# bbg.net
KiCad netlist of a schematic drawn in EAGLE
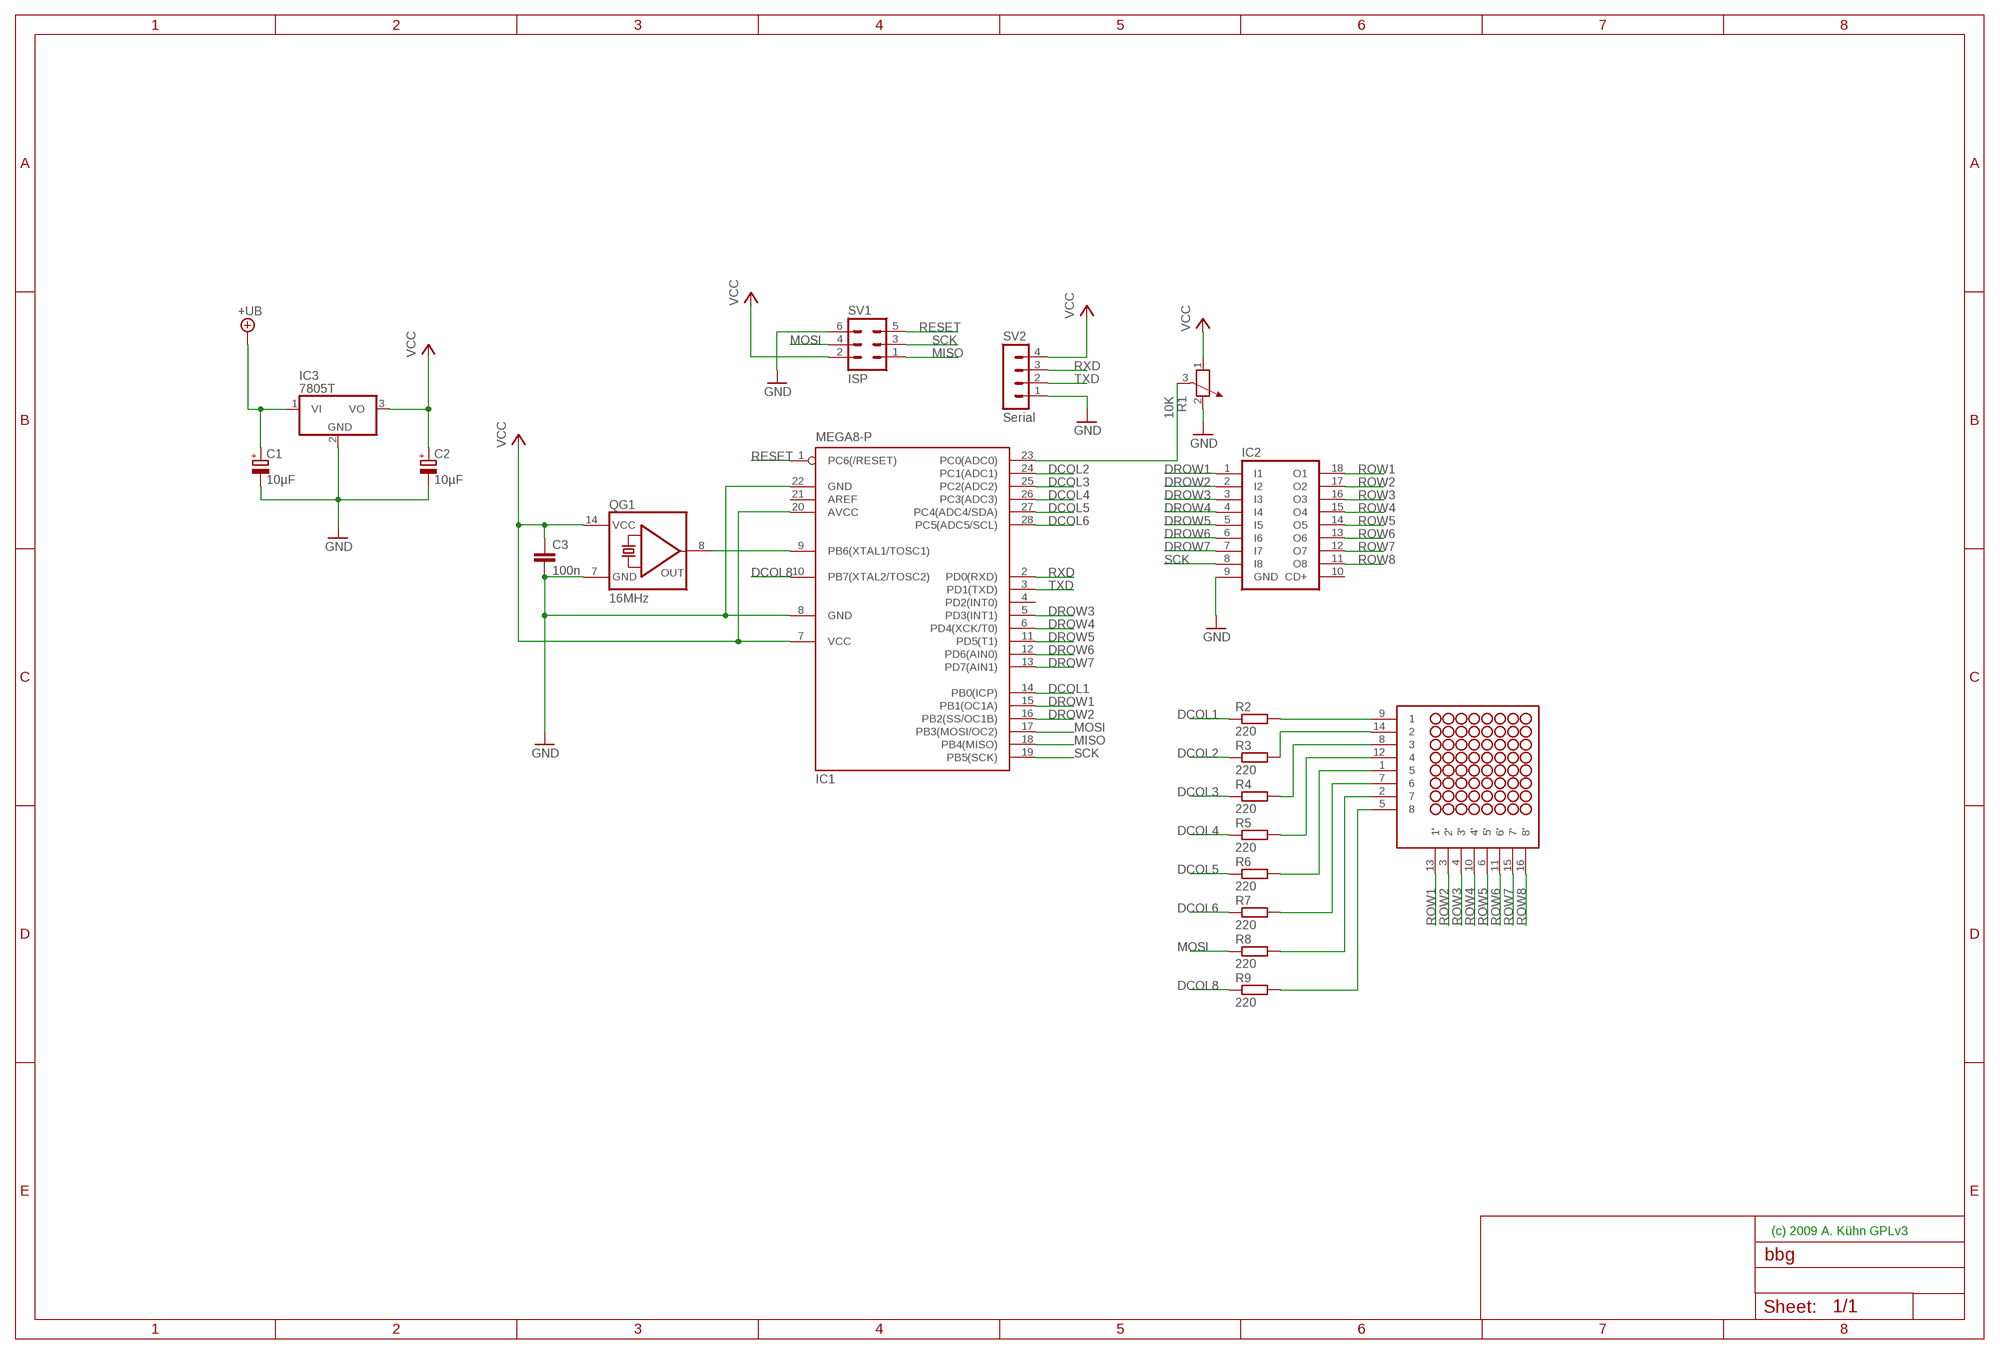
[diagram p0: schematic, sheet 1]

(export (version "E")
  (design (tool "Eeschema 10.0.6"))
  (components
    (comp (ref "C1")
      (value "10µF")
      (footprint "eagle-import:EB20D")
      (libsource (lib "eagle-import") (part "CPOL-EUE10-20"))
    )
    (comp (ref "C2")
      (value "10µF")
      (footprint "eagle-import:EB20D")
      (libsource (lib "eagle-import") (part "CPOL-EUE10-20"))
    )
    (comp (ref "C3")
      (value "100n")
      (footprint "eagle-import:C0603")
      (libsource (lib "eagle-import") (part "C-EUC0603"))
    )
    (comp (ref "IC1")
      (value "MEGA8-P")
      (footprint "eagle-import:DIL28-3")
      (libsource (lib "eagle-import") (part "MEGA8-P"))
    )
    (comp (ref "IC2")
      (value "ULN2803A")
      (footprint "eagle-import:DIL18")
      (libsource (lib "eagle-import") (part "ULN2803A"))
    )
    (comp (ref "IC3")
      (value "7805T")
      (footprint "eagle-import:TO220H")
      (libsource (lib "eagle-import") (part "78T05"))
    )
    (comp (ref "QG1")
      (value "16MHz")
      (footprint "eagle-import:DIL14S")
      (libsource (lib "eagle-import") (part "QG5860"))
    )
    (comp (ref "R1")
      (value "10K")
      (footprint "eagle-import:PT-10")
      (libsource (lib "eagle-import") (part "POTENTIOMETER_PT-10"))
    )
    (comp (ref "R2")
      (value "220")
      (footprint "eagle-import:0204V")
      (libsource (lib "eagle-import") (part "R-EU_0204/2V"))
    )
    (comp (ref "R3")
      (value "220")
      (footprint "eagle-import:0204V")
      (libsource (lib "eagle-import") (part "R-EU_0204/2V"))
    )
    (comp (ref "R4")
      (value "220")
      (footprint "eagle-import:0204V")
      (libsource (lib "eagle-import") (part "R-EU_0204/2V"))
    )
    (comp (ref "R5")
      (value "220")
      (footprint "eagle-import:0204V")
      (libsource (lib "eagle-import") (part "R-EU_0204/2V"))
    )
    (comp (ref "R6")
      (value "220")
      (footprint "eagle-import:0204V")
      (libsource (lib "eagle-import") (part "R-EU_0204/2V"))
    )
    (comp (ref "R7")
      (value "220")
      (footprint "eagle-import:0204V")
      (libsource (lib "eagle-import") (part "R-EU_0204/2V"))
    )
    (comp (ref "R8")
      (value "220")
      (footprint "eagle-import:0204V")
      (libsource (lib "eagle-import") (part "R-EU_0204/2V"))
    )
    (comp (ref "R9")
      (value "220")
      (footprint "eagle-import:0204V")
      (libsource (lib "eagle-import") (part "R-EU_0204/2V"))
    )
    (comp (ref "SV1")
      (value "ISP")
      (footprint "eagle-import:MA03-2")
      (libsource (lib "eagle-import") (part "MA03-2"))
    )
    (comp (ref "SV2")
      (value "Serial")
      (footprint "eagle-import:MA04-1")
      (libsource (lib "eagle-import") (part "MA04-1"))
    )
    (comp (ref "U$1")
      (value "NFM-12881BG-11")
      (footprint "eagle-import:NFM-12881BG-11")
      (libsource (lib "eagle-import") (part "NFM-12881BG-11"))
    )
  )
  (nets
    (net (code "1") (name "+UB") (class "Default")
      (node (ref "C1") (pin "+") (pinfunction "+_+") (pintype "passive"))
      (node (ref "IC3") (pin "1") (pinfunction "VI_1") (pintype "input"))
    )
    (net (code "2") (name "/DCOL1") (class "Default")
      (node (ref "IC1") (pin "14") (pinfunction "PB0(ICP)_14") (pintype "bidirectional"))
      (node (ref "R2") (pin "1") (pinfunction "1_1") (pintype "passive"))
    )
    (net (code "3") (name "/DCOL2") (class "Default")
      (node (ref "IC1") (pin "24") (pinfunction "PC1(ADC1)_24") (pintype "bidirectional"))
      (node (ref "R3") (pin "1") (pinfunction "1_1") (pintype "passive"))
    )
    (net (code "4") (name "/DCOL3") (class "Default")
      (node (ref "IC1") (pin "25") (pinfunction "PC2(ADC2)_25") (pintype "bidirectional"))
      (node (ref "R4") (pin "1") (pinfunction "1_1") (pintype "passive"))
    )
    (net (code "5") (name "/DCOL4") (class "Default")
      (node (ref "IC1") (pin "26") (pinfunction "PC3(ADC3)_26") (pintype "bidirectional"))
      (node (ref "R5") (pin "1") (pinfunction "1_1") (pintype "passive"))
    )
    (net (code "6") (name "/DCOL5") (class "Default")
      (node (ref "IC1") (pin "27") (pinfunction "PC4(ADC4/SDA)_27") (pintype "bidirectional"))
      (node (ref "R6") (pin "1") (pinfunction "1_1") (pintype "passive"))
    )
    (net (code "7") (name "/DCOL6") (class "Default")
      (node (ref "IC1") (pin "28") (pinfunction "PC5(ADC5/SCL)_28") (pintype "bidirectional"))
      (node (ref "R7") (pin "1") (pinfunction "1_1") (pintype "passive"))
    )
    (net (code "8") (name "/DCOL8") (class "Default")
      (node (ref "IC1") (pin "10") (pinfunction "PB7(XTAL2/TOSC2)_10") (pintype "bidirectional"))
      (node (ref "R9") (pin "1") (pinfunction "1_1") (pintype "passive"))
    )
    (net (code "9") (name "/DROW1") (class "Default")
      (node (ref "IC1") (pin "15") (pinfunction "PB1(OC1A)_15") (pintype "bidirectional"))
      (node (ref "IC2") (pin "1") (pinfunction "I1_1") (pintype "input"))
    )
    (net (code "10") (name "/DROW2") (class "Default")
      (node (ref "IC1") (pin "16") (pinfunction "PB2(SS/OC1B)_16") (pintype "bidirectional"))
      (node (ref "IC2") (pin "2") (pinfunction "I2_2") (pintype "input"))
    )
    (net (code "11") (name "/DROW3") (class "Default")
      (node (ref "IC1") (pin "5") (pinfunction "PD3(INT1)_5") (pintype "bidirectional"))
      (node (ref "IC2") (pin "3") (pinfunction "I3_3") (pintype "input"))
    )
    (net (code "12") (name "/DROW4") (class "Default")
      (node (ref "IC1") (pin "6") (pinfunction "PD4(XCK/T0)_6") (pintype "bidirectional"))
      (node (ref "IC2") (pin "4") (pinfunction "I4_4") (pintype "input"))
    )
    (net (code "13") (name "/DROW5") (class "Default")
      (node (ref "IC1") (pin "11") (pinfunction "PD5(T1)_11") (pintype "bidirectional"))
      (node (ref "IC2") (pin "5") (pinfunction "I5_5") (pintype "input"))
    )
    (net (code "14") (name "/DROW6") (class "Default")
      (node (ref "IC1") (pin "12") (pinfunction "PD6(AIN0)_12") (pintype "bidirectional"))
      (node (ref "IC2") (pin "6") (pinfunction "I6_6") (pintype "input"))
    )
    (net (code "15") (name "/DROW7") (class "Default")
      (node (ref "IC1") (pin "13") (pinfunction "PD7(AIN1)_13") (pintype "bidirectional"))
      (node (ref "IC2") (pin "7") (pinfunction "I7_7") (pintype "input"))
    )
    (net (code "16") (name "/MISO") (class "Default")
      (node (ref "IC1") (pin "18") (pinfunction "PB4(MISO)_18") (pintype "bidirectional"))
      (node (ref "SV1") (pin "1") (pinfunction "1_1") (pintype "passive"))
    )
    (net (code "17") (name "/MOSI") (class "Default")
      (node (ref "IC1") (pin "17") (pinfunction "PB3(MOSI/OC2)_17") (pintype "bidirectional"))
      (node (ref "R8") (pin "1") (pinfunction "1_1") (pintype "passive"))
      (node (ref "SV1") (pin "4") (pinfunction "4_4") (pintype "passive"))
    )
    (net (code "18") (name "/RESET") (class "Default")
      (node (ref "IC1") (pin "1") (pinfunction "PC6(/RESET)_1") (pintype "bidirectional"))
      (node (ref "SV1") (pin "5") (pinfunction "5_5") (pintype "passive"))
    )
    (net (code "19") (name "/ROW1") (class "Default")
      (node (ref "IC2") (pin "18") (pinfunction "O1_18") (pintype "open_collector"))
      (node (ref "U$1") (pin "13") (pinfunction "1'_13") (pintype "output"))
    )
    (net (code "20") (name "/ROW2") (class "Default")
      (node (ref "IC2") (pin "17") (pinfunction "O2_17") (pintype "open_collector"))
      (node (ref "U$1") (pin "3") (pinfunction "2'_3") (pintype "output"))
    )
    (net (code "21") (name "/ROW3") (class "Default")
      (node (ref "IC2") (pin "16") (pinfunction "O3_16") (pintype "open_collector"))
      (node (ref "U$1") (pin "4") (pinfunction "3'_4") (pintype "output"))
    )
    (net (code "22") (name "/ROW4") (class "Default")
      (node (ref "IC2") (pin "15") (pinfunction "O4_15") (pintype "open_collector"))
      (node (ref "U$1") (pin "10") (pinfunction "4'_10") (pintype "output"))
    )
    (net (code "23") (name "/ROW5") (class "Default")
      (node (ref "IC2") (pin "14") (pinfunction "O5_14") (pintype "open_collector"))
      (node (ref "U$1") (pin "6") (pinfunction "5'_6") (pintype "output"))
    )
    (net (code "24") (name "/ROW6") (class "Default")
      (node (ref "IC2") (pin "13") (pinfunction "O6_13") (pintype "open_collector"))
      (node (ref "U$1") (pin "11") (pinfunction "6'_11") (pintype "output"))
    )
    (net (code "25") (name "/ROW7") (class "Default")
      (node (ref "IC2") (pin "12") (pinfunction "O7_12") (pintype "open_collector"))
      (node (ref "U$1") (pin "15") (pinfunction "7'_15") (pintype "output"))
    )
    (net (code "26") (name "/ROW8") (class "Default")
      (node (ref "IC2") (pin "11") (pinfunction "O8_11") (pintype "open_collector"))
      (node (ref "U$1") (pin "16") (pinfunction "8'_16") (pintype "output"))
    )
    (net (code "27") (name "/RXD") (class "Default")
      (node (ref "IC1") (pin "2") (pinfunction "PD0(RXD)_2") (pintype "bidirectional"))
      (node (ref "SV2") (pin "3") (pinfunction "3_3") (pintype "passive"))
    )
    (net (code "28") (name "/SCK") (class "Default")
      (node (ref "IC1") (pin "19") (pinfunction "PB5(SCK)_19") (pintype "bidirectional"))
      (node (ref "IC2") (pin "8") (pinfunction "I8_8") (pintype "input"))
      (node (ref "SV1") (pin "3") (pinfunction "3_3") (pintype "passive"))
    )
    (net (code "29") (name "/TXD") (class "Default")
      (node (ref "IC1") (pin "3") (pinfunction "PD1(TXD)_3") (pintype "bidirectional"))
      (node (ref "SV2") (pin "2") (pinfunction "2_2") (pintype "passive"))
    )
    (net (code "30") (name "GND") (class "Default")
      (node (ref "C1") (pin "-") (pinfunction "-_-") (pintype "passive"))
      (node (ref "C2") (pin "-") (pinfunction "-_-") (pintype "passive"))
      (node (ref "C3") (pin "2") (pinfunction "2_2") (pintype "passive"))
      (node (ref "IC1") (pin "22") (pinfunction "GND_22") (pintype "power_in"))
      (node (ref "IC1") (pin "8") (pinfunction "GND_8") (pintype "power_in"))
      (node (ref "IC2") (pin "9") (pinfunction "GND_9") (pintype "power_in"))
      (node (ref "IC3") (pin "2") (pinfunction "GND_2") (pintype "passive"))
      (node (ref "QG1") (pin "7") (pinfunction "GND_7") (pintype "power_in"))
      (node (ref "R1") (pin "2") (pinfunction "2_2") (pintype "passive"))
      (node (ref "SV1") (pin "6") (pinfunction "6_6") (pintype "passive"))
      (node (ref "SV2") (pin "1") (pinfunction "1_1") (pintype "passive"))
    )
    (net (code "31") (name "Net-(IC1-PB6(XTAL1{slash}TOSC1))") (class "Default")
      (node (ref "IC1") (pin "9") (pinfunction "PB6(XTAL1/TOSC1)_9") (pintype "bidirectional"))
      (node (ref "QG1") (pin "8") (pinfunction "OUT_8") (pintype "output"))
    )
    (net (code "32") (name "Net-(IC1-PC0(ADC0))") (class "Default")
      (node (ref "IC1") (pin "23") (pinfunction "PC0(ADC0)_23") (pintype "bidirectional"))
      (node (ref "R1") (pin "3") (pinfunction "3_3") (pintype "passive"))
    )
    (net (code "33") (name "Net-(U$1-1)") (class "Default")
      (node (ref "R2") (pin "2") (pinfunction "2_2") (pintype "passive"))
      (node (ref "U$1") (pin "9") (pinfunction "1_9") (pintype "input"))
    )
    (net (code "34") (name "Net-(U$1-2)") (class "Default")
      (node (ref "R3") (pin "2") (pinfunction "2_2") (pintype "passive"))
      (node (ref "U$1") (pin "14") (pinfunction "2_14") (pintype "input"))
    )
    (net (code "35") (name "Net-(U$1-3)") (class "Default")
      (node (ref "R4") (pin "2") (pinfunction "2_2") (pintype "passive"))
      (node (ref "U$1") (pin "8") (pinfunction "3_8") (pintype "input"))
    )
    (net (code "36") (name "Net-(U$1-4)") (class "Default")
      (node (ref "R5") (pin "2") (pinfunction "2_2") (pintype "passive"))
      (node (ref "U$1") (pin "12") (pinfunction "4_12") (pintype "input"))
    )
    (net (code "37") (name "Net-(U$1-5)") (class "Default")
      (node (ref "R6") (pin "2") (pinfunction "2_2") (pintype "passive"))
      (node (ref "U$1") (pin "1") (pinfunction "5_1") (pintype "input"))
    )
    (net (code "38") (name "Net-(U$1-6)") (class "Default")
      (node (ref "R7") (pin "2") (pinfunction "2_2") (pintype "passive"))
      (node (ref "U$1") (pin "7") (pinfunction "6_7") (pintype "input"))
    )
    (net (code "39") (name "Net-(U$1-7)") (class "Default")
      (node (ref "R8") (pin "2") (pinfunction "2_2") (pintype "passive"))
      (node (ref "U$1") (pin "2") (pinfunction "7_2") (pintype "input"))
    )
    (net (code "40") (name "Net-(U$1-8)") (class "Default")
      (node (ref "R9") (pin "2") (pinfunction "2_2") (pintype "passive"))
      (node (ref "U$1") (pin "5") (pinfunction "8_5") (pintype "input"))
    )
    (net (code "41") (name "VCC") (class "Default")
      (node (ref "C2") (pin "+") (pinfunction "+_+") (pintype "passive"))
      (node (ref "C3") (pin "1") (pinfunction "1_1") (pintype "passive"))
      (node (ref "IC1") (pin "20") (pinfunction "AVCC_20") (pintype "power_in"))
      (node (ref "IC1") (pin "7") (pinfunction "VCC_7") (pintype "power_in"))
      (node (ref "IC3") (pin "3") (pinfunction "VO_3") (pintype "passive"))
      (node (ref "QG1") (pin "14") (pinfunction "VCC_14") (pintype "power_in"))
      (node (ref "R1") (pin "1") (pinfunction "1_1") (pintype "passive"))
      (node (ref "SV1") (pin "2") (pinfunction "2_2") (pintype "passive"))
      (node (ref "SV2") (pin "4") (pinfunction "4_4") (pintype "passive"))
    )
    (net (code "42") (name "unconnected-(IC1-AREF-Pad21)") (class "Default")
      (node (ref "IC1") (pin "21") (pinfunction "AREF_21") (pintype "passive"))
    )
    (net (code "43") (name "unconnected-(IC1-PD2(INT0)-Pad4)") (class "Default")
      (node (ref "IC1") (pin "4") (pinfunction "PD2(INT0)_4") (pintype "bidirectional"))
    )
    (net (code "44") (name "unconnected-(IC2-CD+-Pad10)") (class "Default")
      (node (ref "IC2") (pin "10") (pinfunction "CD+_10") (pintype "passive"))
    )
  )
)
